# SCH_555-Circuit_2026-02-20.net
KiCad netlist of a schematic drawn in EasyEDA
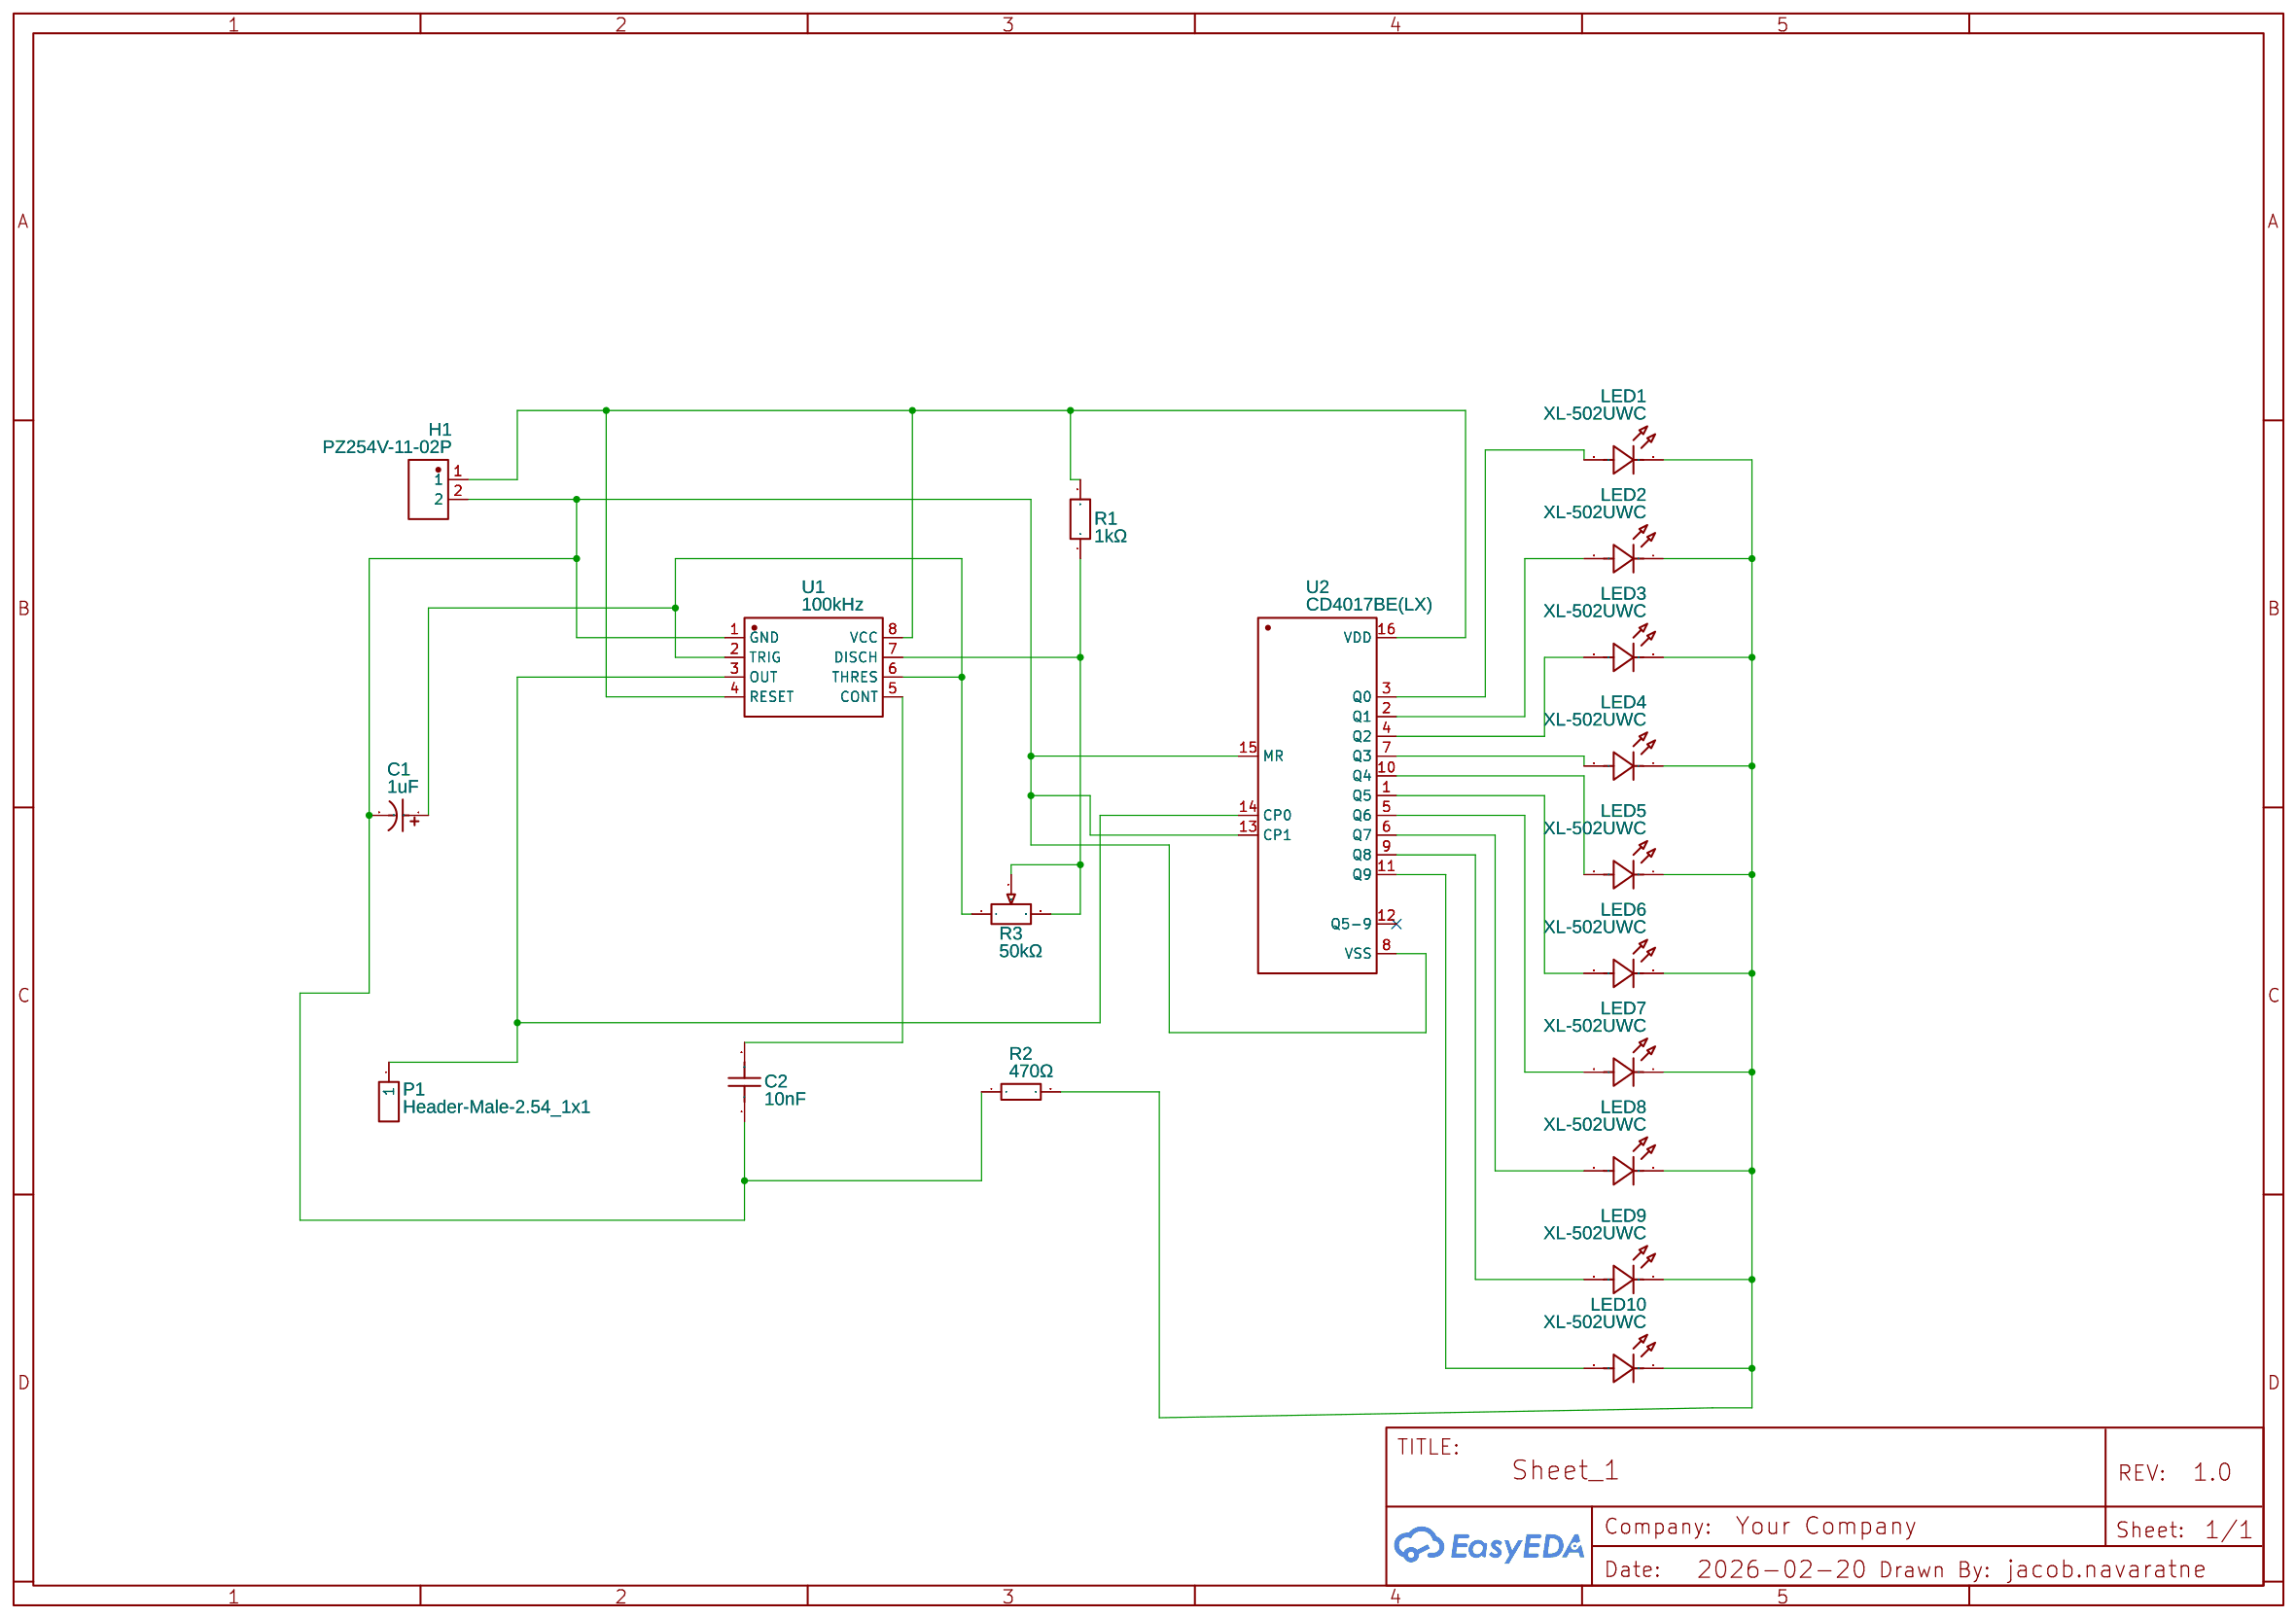
[diagram p0: schematic sheet]

(export (version "E")
  (design (tool "Eeschema 10.0.6"))
  (components
    (comp (ref "C1")
      (value "1uF")
      (fields (field (name "Manufacturer Part") "KF010M050C110A") (field (name "Manufacturer") "CapXon(丰宾)"))
      (libsource (lib "") (part "KF010M050C110A"))
    )
    (comp (ref "C2")
      (value "10nF")
      (fields (field (name "Manufacturer Part") "N09F1B103MN0B0S0N0") (field (name "Manufacturer") "STE(松田)"))
      (libsource (lib "") (part "N09F1B103MN0B0S0N0"))
    )
    (comp (ref "H1")
      (value "PZ254V-11-02P")
      (fields (field (name "Manufacturer") "XFCN(兴飞)"))
      (libsource (lib "") (part "PZ254V-11-02P"))
    )
    (comp (ref "LED1")
      (value "XL-502UWC")
      (fields (field (name "Manufacturer") "XINGLIGHT(成兴光)"))
      (libsource (lib "") (part "XL-502UWC"))
    )
    (comp (ref "LED2")
      (value "XL-502UWC")
      (fields (field (name "Manufacturer") "XINGLIGHT(成兴光)"))
      (libsource (lib "") (part "XL-502UWC"))
    )
    (comp (ref "LED3")
      (value "XL-502UWC")
      (fields (field (name "Manufacturer") "XINGLIGHT(成兴光)"))
      (libsource (lib "") (part "XL-502UWC"))
    )
    (comp (ref "LED4")
      (value "XL-502UWC")
      (fields (field (name "Manufacturer") "XINGLIGHT(成兴光)"))
      (libsource (lib "") (part "XL-502UWC"))
    )
    (comp (ref "LED5")
      (value "XL-502UWC")
      (fields (field (name "Manufacturer") "XINGLIGHT(成兴光)"))
      (libsource (lib "") (part "XL-502UWC"))
    )
    (comp (ref "LED6")
      (value "XL-502UWC")
      (fields (field (name "Manufacturer") "XINGLIGHT(成兴光)"))
      (libsource (lib "") (part "XL-502UWC"))
    )
    (comp (ref "LED7")
      (value "XL-502UWC")
      (fields (field (name "Manufacturer") "XINGLIGHT(成兴光)"))
      (libsource (lib "") (part "XL-502UWC"))
    )
    (comp (ref "LED8")
      (value "XL-502UWC")
      (fields (field (name "Manufacturer") "XINGLIGHT(成兴光)"))
      (libsource (lib "") (part "XL-502UWC"))
    )
    (comp (ref "LED9")
      (value "XL-502UWC")
      (fields (field (name "Manufacturer") "XINGLIGHT(成兴光)"))
      (libsource (lib "") (part "XL-502UWC"))
    )
    (comp (ref "LED10")
      (value "XL-502UWC")
      (fields (field (name "Manufacturer") "XINGLIGHT(成兴光)"))
      (libsource (lib "") (part "XL-502UWC"))
    )
    (comp (ref "P1")
      (value "Header-Male-2.54_1x1")
      (fields (field (name "Manufacturer Part") "2.54-1*1P针") (field (name "Manufacturer") "BOOMELE(博穆精密)"))
      (libsource (lib "") (part "Header-Male-2.54_1x1"))
    )
    (comp (ref "R1")
      (value "1kΩ")
      (fields (field (name "Manufacturer Part") "MF1/4W-1KΩ±1%T52") (field (name "Manufacturer") "华星机电"))
      (libsource (lib "") (part "MF1/4W-1KΩ±1%T52"))
    )
    (comp (ref "R2")
      (value "470Ω")
      (fields
        (field (name "Manufacturer Part") "MFR0W4F4700A50")
        (field (name "Manufacturer") "UNI-ROYAL(厚声)")
      )
      (libsource (lib "") (part "MFR0W4F4700A50"))
    )
    (comp (ref "R3")
      (value "50kΩ")
      (fields (field (name "Manufacturer Part") "3296X-1-503") (field (name "Manufacturer") "BOCHEN(博晨)"))
      (libsource (lib "") (part "3296X-1-503_C118912"))
    )
    (comp (ref "U1")
      (value "100kHz")
      (fields (field (name "Manufacturer Part") "NE555P") (field (name "Manufacturer") "TI(德州仪器)"))
      (libsource (lib "") (part "NE555P"))
    )
    (comp (ref "U2")
      (value "CD4017BE(LX)")
      (fields (field (name "Manufacturer") "LX(灵星芯微)"))
      (libsource (lib "") (part "CD4017BE(LX)"))
    )
  )
  (nets
    (net (code "1") (name "Net-(LED1-A)") (class "Default")
      (node (ref "LED1") (pin "2") (pinfunction "A_2") (pintype "unspecified"))
      (node (ref "U2") (pin "3") (pinfunction "Q0_3") (pintype "unspecified"))
    )
    (net (code "2") (name "Net-(LED1-K)") (class "Default")
      (node (ref "LED1") (pin "1") (pinfunction "K_1") (pintype "unspecified"))
      (node (ref "LED10") (pin "1") (pinfunction "K_1") (pintype "unspecified"))
      (node (ref "LED2") (pin "1") (pinfunction "K_1") (pintype "unspecified"))
      (node (ref "LED3") (pin "1") (pinfunction "K_1") (pintype "unspecified"))
      (node (ref "LED4") (pin "1") (pinfunction "K_1") (pintype "unspecified"))
      (node (ref "LED5") (pin "1") (pinfunction "K_1") (pintype "unspecified"))
      (node (ref "LED6") (pin "1") (pinfunction "K_1") (pintype "unspecified"))
      (node (ref "LED7") (pin "1") (pinfunction "K_1") (pintype "unspecified"))
      (node (ref "LED8") (pin "1") (pinfunction "K_1") (pintype "unspecified"))
      (node (ref "LED9") (pin "1") (pinfunction "K_1") (pintype "unspecified"))
      (node (ref "R2") (pin "2") (pinfunction "2_2") (pintype "input"))
    )
    (net (code "3") (name "Net-(LED2-A)") (class "Default")
      (node (ref "LED2") (pin "2") (pinfunction "A_2") (pintype "unspecified"))
      (node (ref "U2") (pin "2") (pinfunction "Q1_2") (pintype "unspecified"))
    )
    (net (code "4") (name "Net-(LED3-A)") (class "Default")
      (node (ref "LED3") (pin "2") (pinfunction "A_2") (pintype "unspecified"))
      (node (ref "U2") (pin "4") (pinfunction "Q2_4") (pintype "unspecified"))
    )
    (net (code "5") (name "Net-(LED4-A)") (class "Default")
      (node (ref "LED4") (pin "2") (pinfunction "A_2") (pintype "unspecified"))
      (node (ref "U2") (pin "7") (pinfunction "Q3_7") (pintype "unspecified"))
    )
    (net (code "6") (name "Net-(LED5-A)") (class "Default")
      (node (ref "LED5") (pin "2") (pinfunction "A_2") (pintype "unspecified"))
      (node (ref "U2") (pin "10") (pinfunction "Q4_10") (pintype "unspecified"))
    )
    (net (code "7") (name "Net-(LED6-A)") (class "Default")
      (node (ref "LED6") (pin "2") (pinfunction "A_2") (pintype "unspecified"))
      (node (ref "U2") (pin "1") (pinfunction "Q5_1") (pintype "unspecified"))
    )
    (net (code "8") (name "Net-(LED7-A)") (class "Default")
      (node (ref "LED7") (pin "2") (pinfunction "A_2") (pintype "unspecified"))
      (node (ref "U2") (pin "5") (pinfunction "Q6_5") (pintype "unspecified"))
    )
    (net (code "9") (name "Net-(LED8-A)") (class "Default")
      (node (ref "LED8") (pin "2") (pinfunction "A_2") (pintype "unspecified"))
      (node (ref "U2") (pin "6") (pinfunction "Q7_6") (pintype "unspecified"))
    )
    (net (code "10") (name "Net-(LED9-A)") (class "Default")
      (node (ref "LED9") (pin "2") (pinfunction "A_2") (pintype "unspecified"))
      (node (ref "U2") (pin "9") (pinfunction "Q8_9") (pintype "unspecified"))
    )
    (net (code "11") (name "Net-(LED10-A)") (class "Default")
      (node (ref "LED10") (pin "2") (pinfunction "A_2") (pintype "unspecified"))
      (node (ref "U2") (pin "11") (pinfunction "Q9_11") (pintype "unspecified"))
    )
    (net (code "12") (name "Net-(U1-CONT)") (class "Default")
      (node (ref "C2") (pin "2") (pinfunction "2_2") (pintype "unspecified"))
      (node (ref "U1") (pin "5") (pinfunction "CONT_5") (pintype "unspecified"))
    )
    (net (code "13") (name "Net-(U1-DISCH)") (class "Default")
      (node (ref "R1") (pin "1") (pinfunction "1_1") (pintype "unspecified"))
      (node (ref "R3") (pin "2") (pinfunction "2_2") (pintype "input"))
      (node (ref "R3") (pin "3") (pinfunction "3_3") (pintype "input"))
      (node (ref "U1") (pin "7") (pinfunction "DISCH_7") (pintype "unspecified"))
    )
    (net (code "14") (name "Net-(U1-GND)") (class "Default")
      (node (ref "C1") (pin "2") (pinfunction "2_2") (pintype "input"))
      (node (ref "C2") (pin "1") (pinfunction "1_1") (pintype "unspecified"))
      (node (ref "H1") (pin "2") (pinfunction "2_2") (pintype "unspecified"))
      (node (ref "R2") (pin "1") (pinfunction "1_1") (pintype "input"))
      (node (ref "U1") (pin "1") (pinfunction "GND_1") (pintype "unspecified"))
      (node (ref "U2") (pin "13") (pinfunction "CP1_13") (pintype "unspecified"))
      (node (ref "U2") (pin "15") (pinfunction "MR_15") (pintype "unspecified"))
      (node (ref "U2") (pin "8") (pinfunction "VSS_8") (pintype "unspecified"))
    )
    (net (code "15") (name "Net-(U1-OUT)") (class "Default")
      (node (ref "P1") (pin "1") (pinfunction "1_1") (pintype "input"))
      (node (ref "U1") (pin "3") (pinfunction "OUT_3") (pintype "unspecified"))
      (node (ref "U2") (pin "14") (pinfunction "CP0_14") (pintype "unspecified"))
    )
    (net (code "16") (name "Net-(U1-RESET)") (class "Default")
      (node (ref "H1") (pin "1") (pinfunction "1_1") (pintype "unspecified"))
      (node (ref "R1") (pin "2") (pinfunction "2_2") (pintype "unspecified"))
      (node (ref "U1") (pin "4") (pinfunction "RESET_4") (pintype "unspecified"))
      (node (ref "U1") (pin "8") (pinfunction "VCC_8") (pintype "unspecified"))
      (node (ref "U2") (pin "16") (pinfunction "VDD_16") (pintype "unspecified"))
    )
    (net (code "17") (name "Net-(U1-THRES)") (class "Default")
      (node (ref "C1") (pin "1") (pinfunction "1_1") (pintype "input"))
      (node (ref "R3") (pin "1") (pinfunction "1_1") (pintype "input"))
      (node (ref "U1") (pin "2") (pinfunction "TRIG_2") (pintype "unspecified"))
      (node (ref "U1") (pin "6") (pinfunction "THRES_6") (pintype "unspecified"))
    )
    (net (code "18") (name "unconnected-(U2-Q5-9-Pad12)") (class "Default")
      (node (ref "U2") (pin "12") (pinfunction "Q5-9_12") (pintype "unspecified+no_connect"))
    )
  )
)
